# ten_peg_board.net
KiCad netlist of a schematic drawn in EAGLE
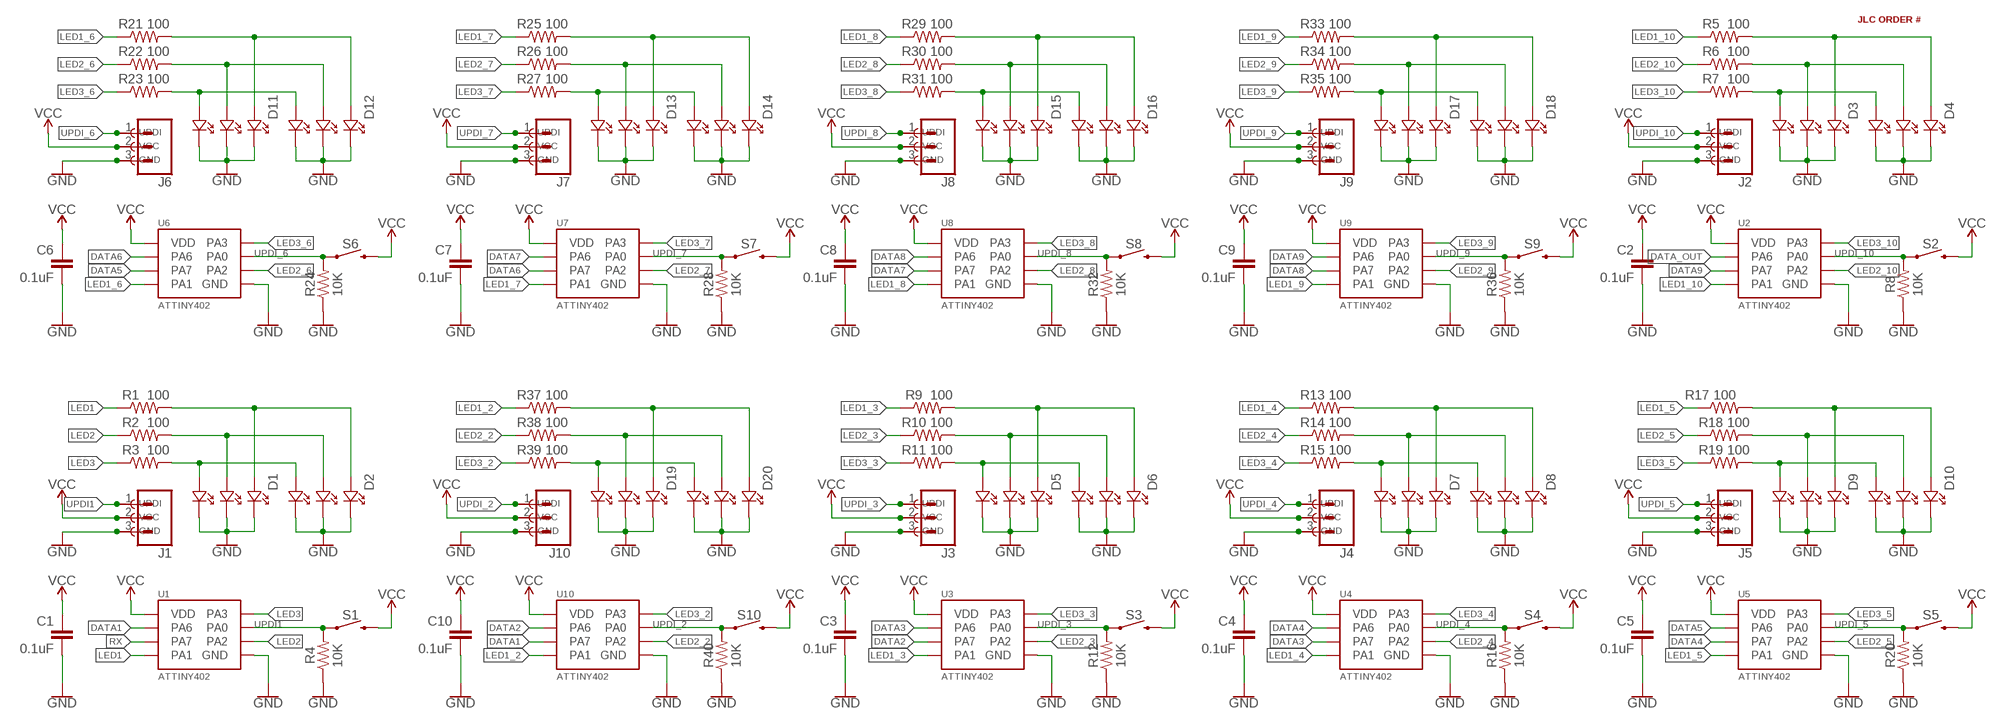
[diagram p0: schematic, sheet 1]

(export (version "E")
  (design (tool "Eeschema 10.0.6"))
  (components
    (comp (ref "C1")
      (value "0.1uF")
      (footprint "eagle-import:0603")
      (libsource (lib "eagle-import") (part "0.1UF-0603-25V-(+80/-20%)"))
    )
    (comp (ref "C2")
      (value "0.1uF")
      (footprint "eagle-import:0603")
      (libsource (lib "eagle-import") (part "0.1UF-0603-25V-(+80/-20%)"))
    )
    (comp (ref "C3")
      (value "0.1uF")
      (footprint "eagle-import:0603")
      (libsource (lib "eagle-import") (part "0.1UF-0603-25V-(+80/-20%)"))
    )
    (comp (ref "C4")
      (value "0.1uF")
      (footprint "eagle-import:0603")
      (libsource (lib "eagle-import") (part "0.1UF-0603-25V-(+80/-20%)"))
    )
    (comp (ref "C5")
      (value "0.1uF")
      (footprint "eagle-import:0603")
      (libsource (lib "eagle-import") (part "0.1UF-0603-25V-(+80/-20%)"))
    )
    (comp (ref "C6")
      (value "0.1uF")
      (footprint "eagle-import:0603")
      (libsource (lib "eagle-import") (part "0.1UF-0603-25V-(+80/-20%)"))
    )
    (comp (ref "C7")
      (value "0.1uF")
      (footprint "eagle-import:0603")
      (libsource (lib "eagle-import") (part "0.1UF-0603-25V-(+80/-20%)"))
    )
    (comp (ref "C8")
      (value "0.1uF")
      (footprint "eagle-import:0603")
      (libsource (lib "eagle-import") (part "0.1UF-0603-25V-(+80/-20%)"))
    )
    (comp (ref "C9")
      (value "0.1uF")
      (footprint "eagle-import:0603")
      (libsource (lib "eagle-import") (part "0.1UF-0603-25V-(+80/-20%)"))
    )
    (comp (ref "C10")
      (value "0.1uF")
      (footprint "eagle-import:0603")
      (libsource (lib "eagle-import") (part "0.1UF-0603-25V-(+80/-20%)"))
    )
    (comp (ref "D1")
      (value "19-337C/RSBHGHC-A88/4T")
      (footprint "eagle-import:6-SMD")
      (libsource (lib "eagle-import") (part "19-337C/RSBHGHC-A88/4T"))
    )
    (comp (ref "D2")
      (value "19-337C/RSBHGHC-A88/4T")
      (footprint "eagle-import:6-SMD")
      (libsource (lib "eagle-import") (part "19-337C/RSBHGHC-A88/4T"))
    )
    (comp (ref "D3")
      (value "19-337C/RSBHGHC-A88/4T")
      (footprint "eagle-import:6-SMD")
      (libsource (lib "eagle-import") (part "19-337C/RSBHGHC-A88/4T"))
    )
    (comp (ref "D4")
      (value "19-337C/RSBHGHC-A88/4T")
      (footprint "eagle-import:6-SMD")
      (libsource (lib "eagle-import") (part "19-337C/RSBHGHC-A88/4T"))
    )
    (comp (ref "D5")
      (value "19-337C/RSBHGHC-A88/4T")
      (footprint "eagle-import:6-SMD")
      (libsource (lib "eagle-import") (part "19-337C/RSBHGHC-A88/4T"))
    )
    (comp (ref "D6")
      (value "19-337C/RSBHGHC-A88/4T")
      (footprint "eagle-import:6-SMD")
      (libsource (lib "eagle-import") (part "19-337C/RSBHGHC-A88/4T"))
    )
    (comp (ref "D7")
      (value "19-337C/RSBHGHC-A88/4T")
      (footprint "eagle-import:6-SMD")
      (libsource (lib "eagle-import") (part "19-337C/RSBHGHC-A88/4T"))
    )
    (comp (ref "D8")
      (value "19-337C/RSBHGHC-A88/4T")
      (footprint "eagle-import:6-SMD")
      (libsource (lib "eagle-import") (part "19-337C/RSBHGHC-A88/4T"))
    )
    (comp (ref "D9")
      (value "19-337C/RSBHGHC-A88/4T")
      (footprint "eagle-import:6-SMD")
      (libsource (lib "eagle-import") (part "19-337C/RSBHGHC-A88/4T"))
    )
    (comp (ref "D10")
      (value "19-337C/RSBHGHC-A88/4T")
      (footprint "eagle-import:6-SMD")
      (libsource (lib "eagle-import") (part "19-337C/RSBHGHC-A88/4T"))
    )
    (comp (ref "D11")
      (value "19-337C/RSBHGHC-A88/4T")
      (footprint "eagle-import:6-SMD")
      (libsource (lib "eagle-import") (part "19-337C/RSBHGHC-A88/4T"))
    )
    (comp (ref "D12")
      (value "19-337C/RSBHGHC-A88/4T")
      (footprint "eagle-import:6-SMD")
      (libsource (lib "eagle-import") (part "19-337C/RSBHGHC-A88/4T"))
    )
    (comp (ref "D13")
      (value "19-337C/RSBHGHC-A88/4T")
      (footprint "eagle-import:6-SMD")
      (libsource (lib "eagle-import") (part "19-337C/RSBHGHC-A88/4T"))
    )
    (comp (ref "D14")
      (value "19-337C/RSBHGHC-A88/4T")
      (footprint "eagle-import:6-SMD")
      (libsource (lib "eagle-import") (part "19-337C/RSBHGHC-A88/4T"))
    )
    (comp (ref "D15")
      (value "19-337C/RSBHGHC-A88/4T")
      (footprint "eagle-import:6-SMD")
      (libsource (lib "eagle-import") (part "19-337C/RSBHGHC-A88/4T"))
    )
    (comp (ref "D16")
      (value "19-337C/RSBHGHC-A88/4T")
      (footprint "eagle-import:6-SMD")
      (libsource (lib "eagle-import") (part "19-337C/RSBHGHC-A88/4T"))
    )
    (comp (ref "D17")
      (value "19-337C/RSBHGHC-A88/4T")
      (footprint "eagle-import:6-SMD")
      (libsource (lib "eagle-import") (part "19-337C/RSBHGHC-A88/4T"))
    )
    (comp (ref "D18")
      (value "19-337C/RSBHGHC-A88/4T")
      (footprint "eagle-import:6-SMD")
      (libsource (lib "eagle-import") (part "19-337C/RSBHGHC-A88/4T"))
    )
    (comp (ref "D19")
      (value "19-337C/RSBHGHC-A88/4T")
      (footprint "eagle-import:6-SMD")
      (libsource (lib "eagle-import") (part "19-337C/RSBHGHC-A88/4T"))
    )
    (comp (ref "D20")
      (value "19-337C/RSBHGHC-A88/4T")
      (footprint "eagle-import:6-SMD")
      (libsource (lib "eagle-import") (part "19-337C/RSBHGHC-A88/4T"))
    )
    (comp (ref "J1")
      (value "CONN_03LOCK_LONGPADS")
      (footprint "eagle-import:1X03_LOCK_LONGPADS")
      (libsource (lib "eagle-import") (part "CONN_03LOCK_LONGPADS"))
    )
    (comp (ref "J2")
      (value "CONN_03LOCK_LONGPADS")
      (footprint "eagle-import:1X03_LOCK_LONGPADS")
      (libsource (lib "eagle-import") (part "CONN_03LOCK_LONGPADS"))
    )
    (comp (ref "J3")
      (value "CONN_03LOCK_LONGPADS")
      (footprint "eagle-import:1X03_LOCK_LONGPADS")
      (libsource (lib "eagle-import") (part "CONN_03LOCK_LONGPADS"))
    )
    (comp (ref "J4")
      (value "CONN_03LOCK_LONGPADS")
      (footprint "eagle-import:1X03_LOCK_LONGPADS")
      (libsource (lib "eagle-import") (part "CONN_03LOCK_LONGPADS"))
    )
    (comp (ref "J5")
      (value "CONN_03LOCK_LONGPADS")
      (footprint "eagle-import:1X03_LOCK_LONGPADS")
      (libsource (lib "eagle-import") (part "CONN_03LOCK_LONGPADS"))
    )
    (comp (ref "J6")
      (value "CONN_03LOCK_LONGPADS")
      (footprint "eagle-import:1X03_LOCK_LONGPADS")
      (libsource (lib "eagle-import") (part "CONN_03LOCK_LONGPADS"))
    )
    (comp (ref "J7")
      (value "CONN_03LOCK_LONGPADS")
      (footprint "eagle-import:1X03_LOCK_LONGPADS")
      (libsource (lib "eagle-import") (part "CONN_03LOCK_LONGPADS"))
    )
    (comp (ref "J8")
      (value "CONN_03LOCK_LONGPADS")
      (footprint "eagle-import:1X03_LOCK_LONGPADS")
      (libsource (lib "eagle-import") (part "CONN_03LOCK_LONGPADS"))
    )
    (comp (ref "J9")
      (value "CONN_03LOCK_LONGPADS")
      (footprint "eagle-import:1X03_LOCK_LONGPADS")
      (libsource (lib "eagle-import") (part "CONN_03LOCK_LONGPADS"))
    )
    (comp (ref "J10")
      (value "CONN_03LOCK_LONGPADS")
      (footprint "eagle-import:1X03_LOCK_LONGPADS")
      (libsource (lib "eagle-import") (part "CONN_03LOCK_LONGPADS"))
    )
    (comp (ref "R1")
      (value "100")
      (footprint "eagle-import:0603")
      (libsource (lib "eagle-import") (part "100OHM-0603-1/4W-5%"))
    )
    (comp (ref "R2")
      (value "100")
      (footprint "eagle-import:0603")
      (libsource (lib "eagle-import") (part "100OHM-0603-1/4W-5%"))
    )
    (comp (ref "R3")
      (value "100")
      (footprint "eagle-import:0603")
      (libsource (lib "eagle-import") (part "100OHM-0603-1/4W-5%"))
    )
    (comp (ref "R4")
      (value "10K")
      (footprint "eagle-import:0603")
      (libsource (lib "eagle-import") (part "100OHM-0603-1/4W-5%"))
    )
    (comp (ref "R5")
      (value "100")
      (footprint "eagle-import:0603")
      (libsource (lib "eagle-import") (part "100OHM-0603-1/4W-5%"))
    )
    (comp (ref "R6")
      (value "100")
      (footprint "eagle-import:0603")
      (libsource (lib "eagle-import") (part "100OHM-0603-1/4W-5%"))
    )
    (comp (ref "R7")
      (value "100")
      (footprint "eagle-import:0603")
      (libsource (lib "eagle-import") (part "100OHM-0603-1/4W-5%"))
    )
    (comp (ref "R8")
      (value "10K")
      (footprint "eagle-import:0603")
      (libsource (lib "eagle-import") (part "100OHM-0603-1/4W-5%"))
    )
    (comp (ref "R9")
      (value "100")
      (footprint "eagle-import:0603")
      (libsource (lib "eagle-import") (part "100OHM-0603-1/4W-5%"))
    )
    (comp (ref "R10")
      (value "100")
      (footprint "eagle-import:0603")
      (libsource (lib "eagle-import") (part "100OHM-0603-1/4W-5%"))
    )
    (comp (ref "R11")
      (value "100")
      (footprint "eagle-import:0603")
      (libsource (lib "eagle-import") (part "100OHM-0603-1/4W-5%"))
    )
    (comp (ref "R12")
      (value "10K")
      (footprint "eagle-import:0603")
      (libsource (lib "eagle-import") (part "100OHM-0603-1/4W-5%"))
    )
    (comp (ref "R13")
      (value "100")
      (footprint "eagle-import:0603")
      (libsource (lib "eagle-import") (part "100OHM-0603-1/4W-5%"))
    )
    (comp (ref "R14")
      (value "100")
      (footprint "eagle-import:0603")
      (libsource (lib "eagle-import") (part "100OHM-0603-1/4W-5%"))
    )
    (comp (ref "R15")
      (value "100")
      (footprint "eagle-import:0603")
      (libsource (lib "eagle-import") (part "100OHM-0603-1/4W-5%"))
    )
    (comp (ref "R16")
      (value "10K")
      (footprint "eagle-import:0603")
      (libsource (lib "eagle-import") (part "100OHM-0603-1/4W-5%"))
    )
    (comp (ref "R17")
      (value "100")
      (footprint "eagle-import:0603")
      (libsource (lib "eagle-import") (part "100OHM-0603-1/4W-5%"))
    )
    (comp (ref "R18")
      (value "100")
      (footprint "eagle-import:0603")
      (libsource (lib "eagle-import") (part "100OHM-0603-1/4W-5%"))
    )
    (comp (ref "R19")
      (value "100")
      (footprint "eagle-import:0603")
      (libsource (lib "eagle-import") (part "100OHM-0603-1/4W-5%"))
    )
    (comp (ref "R20")
      (value "10K")
      (footprint "eagle-import:0603")
      (libsource (lib "eagle-import") (part "100OHM-0603-1/4W-5%"))
    )
    (comp (ref "R21")
      (value "100")
      (footprint "eagle-import:0603")
      (libsource (lib "eagle-import") (part "100OHM-0603-1/4W-5%"))
    )
    (comp (ref "R22")
      (value "100")
      (footprint "eagle-import:0603")
      (libsource (lib "eagle-import") (part "100OHM-0603-1/4W-5%"))
    )
    (comp (ref "R23")
      (value "100")
      (footprint "eagle-import:0603")
      (libsource (lib "eagle-import") (part "100OHM-0603-1/4W-5%"))
    )
    (comp (ref "R24")
      (value "10K")
      (footprint "eagle-import:0603")
      (libsource (lib "eagle-import") (part "100OHM-0603-1/4W-5%"))
    )
    (comp (ref "R25")
      (value "100")
      (footprint "eagle-import:0603")
      (libsource (lib "eagle-import") (part "100OHM-0603-1/4W-5%"))
    )
    (comp (ref "R26")
      (value "100")
      (footprint "eagle-import:0603")
      (libsource (lib "eagle-import") (part "100OHM-0603-1/4W-5%"))
    )
    (comp (ref "R27")
      (value "100")
      (footprint "eagle-import:0603")
      (libsource (lib "eagle-import") (part "100OHM-0603-1/4W-5%"))
    )
    (comp (ref "R28")
      (value "10K")
      (footprint "eagle-import:0603")
      (libsource (lib "eagle-import") (part "100OHM-0603-1/4W-5%"))
    )
    (comp (ref "R29")
      (value "100")
      (footprint "eagle-import:0603")
      (libsource (lib "eagle-import") (part "100OHM-0603-1/4W-5%"))
    )
    (comp (ref "R30")
      (value "100")
      (footprint "eagle-import:0603")
      (libsource (lib "eagle-import") (part "100OHM-0603-1/4W-5%"))
    )
    (comp (ref "R31")
      (value "100")
      (footprint "eagle-import:0603")
      (libsource (lib "eagle-import") (part "100OHM-0603-1/4W-5%"))
    )
    (comp (ref "R32")
      (value "10K")
      (footprint "eagle-import:0603")
      (libsource (lib "eagle-import") (part "100OHM-0603-1/4W-5%"))
    )
    (comp (ref "R33")
      (value "100")
      (footprint "eagle-import:0603")
      (libsource (lib "eagle-import") (part "100OHM-0603-1/4W-5%"))
    )
    (comp (ref "R34")
      (value "100")
      (footprint "eagle-import:0603")
      (libsource (lib "eagle-import") (part "100OHM-0603-1/4W-5%"))
    )
    (comp (ref "R35")
      (value "100")
      (footprint "eagle-import:0603")
      (libsource (lib "eagle-import") (part "100OHM-0603-1/4W-5%"))
    )
    (comp (ref "R36")
      (value "10K")
      (footprint "eagle-import:0603")
      (libsource (lib "eagle-import") (part "100OHM-0603-1/4W-5%"))
    )
    (comp (ref "R37")
      (value "100")
      (footprint "eagle-import:0603")
      (libsource (lib "eagle-import") (part "100OHM-0603-1/4W-5%"))
    )
    (comp (ref "R38")
      (value "100")
      (footprint "eagle-import:0603")
      (libsource (lib "eagle-import") (part "100OHM-0603-1/4W-5%"))
    )
    (comp (ref "R39")
      (value "100")
      (footprint "eagle-import:0603")
      (libsource (lib "eagle-import") (part "100OHM-0603-1/4W-5%"))
    )
    (comp (ref "R40")
      (value "10K")
      (footprint "eagle-import:0603")
      (libsource (lib "eagle-import") (part "100OHM-0603-1/4W-5%"))
    )
    (comp (ref "S1")
      (value "MOMENTARY-SWITCH-SPST-SMD-4.5MM-WINGED")
      (footprint "eagle-import:TACTILE_SWITCH_SMD_4.5MM_WINGED")
      (libsource (lib "eagle-import") (part "MOMENTARY-SWITCH-SPST-SMD-4.5MM-WINGED"))
    )
    (comp (ref "S2")
      (value "MOMENTARY-SWITCH-SPST-SMD-4.5MM-WINGED")
      (footprint "eagle-import:TACTILE_SWITCH_SMD_4.5MM_WINGED")
      (libsource (lib "eagle-import") (part "MOMENTARY-SWITCH-SPST-SMD-4.5MM-WINGED"))
    )
    (comp (ref "S3")
      (value "MOMENTARY-SWITCH-SPST-SMD-4.5MM-WINGED")
      (footprint "eagle-import:TACTILE_SWITCH_SMD_4.5MM_WINGED")
      (libsource (lib "eagle-import") (part "MOMENTARY-SWITCH-SPST-SMD-4.5MM-WINGED"))
    )
    (comp (ref "S4")
      (value "MOMENTARY-SWITCH-SPST-SMD-4.5MM-WINGED")
      (footprint "eagle-import:TACTILE_SWITCH_SMD_4.5MM_WINGED")
      (libsource (lib "eagle-import") (part "MOMENTARY-SWITCH-SPST-SMD-4.5MM-WINGED"))
    )
    (comp (ref "S5")
      (value "MOMENTARY-SWITCH-SPST-SMD-4.5MM-WINGED")
      (footprint "eagle-import:TACTILE_SWITCH_SMD_4.5MM_WINGED")
      (libsource (lib "eagle-import") (part "MOMENTARY-SWITCH-SPST-SMD-4.5MM-WINGED"))
    )
    (comp (ref "S6")
      (value "MOMENTARY-SWITCH-SPST-SMD-4.5MM-WINGED")
      (footprint "eagle-import:TACTILE_SWITCH_SMD_4.5MM_WINGED")
      (libsource (lib "eagle-import") (part "MOMENTARY-SWITCH-SPST-SMD-4.5MM-WINGED"))
    )
    (comp (ref "S7")
      (value "MOMENTARY-SWITCH-SPST-SMD-4.5MM-WINGED")
      (footprint "eagle-import:TACTILE_SWITCH_SMD_4.5MM_WINGED")
      (libsource (lib "eagle-import") (part "MOMENTARY-SWITCH-SPST-SMD-4.5MM-WINGED"))
    )
    (comp (ref "S8")
      (value "MOMENTARY-SWITCH-SPST-SMD-4.5MM-WINGED")
      (footprint "eagle-import:TACTILE_SWITCH_SMD_4.5MM_WINGED")
      (libsource (lib "eagle-import") (part "MOMENTARY-SWITCH-SPST-SMD-4.5MM-WINGED"))
    )
    (comp (ref "S9")
      (value "MOMENTARY-SWITCH-SPST-SMD-4.5MM-WINGED")
      (footprint "eagle-import:TACTILE_SWITCH_SMD_4.5MM_WINGED")
      (libsource (lib "eagle-import") (part "MOMENTARY-SWITCH-SPST-SMD-4.5MM-WINGED"))
    )
    (comp (ref "S10")
      (value "MOMENTARY-SWITCH-SPST-SMD-4.5MM-WINGED")
      (footprint "eagle-import:TACTILE_SWITCH_SMD_4.5MM_WINGED")
      (libsource (lib "eagle-import") (part "MOMENTARY-SWITCH-SPST-SMD-4.5MM-WINGED"))
    )
    (comp (ref "TP1")
      (value "TEST-POINT3X5")
      (footprint "eagle-import:PAD.03X.05")
      (libsource (lib "eagle-import") (part "TEST-POINT3X5"))
    )
    (comp (ref "TP2")
      (value "TEST-POINT3X5")
      (footprint "eagle-import:PAD.03X.05")
      (libsource (lib "eagle-import") (part "TEST-POINT3X5"))
    )
    (comp (ref "TP3")
      (value "TEST-POINT3X5")
      (footprint "eagle-import:PAD.03X.05")
      (libsource (lib "eagle-import") (part "TEST-POINT3X5"))
    )
    (comp (ref "TP4")
      (value "TEST-POINT3X5")
      (footprint "eagle-import:PAD.03X.05")
      (libsource (lib "eagle-import") (part "TEST-POINT3X5"))
    )
    (comp (ref "TP5")
      (value "TEST-POINT3X5")
      (footprint "eagle-import:PAD.03X.05")
      (libsource (lib "eagle-import") (part "TEST-POINT3X5"))
    )
    (comp (ref "TP6")
      (value "TEST-POINT3X5")
      (footprint "eagle-import:PAD.03X.05")
      (libsource (lib "eagle-import") (part "TEST-POINT3X5"))
    )
    (comp (ref "TP7")
      (value "TEST-POINT3X5")
      (footprint "eagle-import:PAD.03X.05")
      (libsource (lib "eagle-import") (part "TEST-POINT3X5"))
    )
    (comp (ref "TP8")
      (value "TEST-POINT3X5")
      (footprint "eagle-import:PAD.03X.05")
      (libsource (lib "eagle-import") (part "TEST-POINT3X5"))
    )
    (comp (ref "TP9")
      (value "TEST-POINT3X5")
      (footprint "eagle-import:PAD.03X.05")
      (libsource (lib "eagle-import") (part "TEST-POINT3X5"))
    )
    (comp (ref "TP10")
      (value "TEST-POINT3X5")
      (footprint "eagle-import:PAD.03X.05")
      (libsource (lib "eagle-import") (part "TEST-POINT3X5"))
    )
    (comp (ref "TP11")
      (value "TEST-POINT3X5")
      (footprint "eagle-import:PAD.03X.05")
      (libsource (lib "eagle-import") (part "TEST-POINT3X5"))
    )
    (comp (ref "TP12")
      (value "TEST-POINT3X5")
      (footprint "eagle-import:PAD.03X.05")
      (libsource (lib "eagle-import") (part "TEST-POINT3X5"))
    )
    (comp (ref "TP13")
      (value "TEST-POINT3X5")
      (footprint "eagle-import:PAD.03X.05")
      (libsource (lib "eagle-import") (part "TEST-POINT3X5"))
    )
    (comp (ref "TP14")
      (value "TEST-POINT3X5")
      (footprint "eagle-import:PAD.03X.05")
      (libsource (lib "eagle-import") (part "TEST-POINT3X5"))
    )
    (comp (ref "TP15")
      (value "TEST-POINT3X5")
      (footprint "eagle-import:PAD.03X.05")
      (libsource (lib "eagle-import") (part "TEST-POINT3X5"))
    )
    (comp (ref "TP16")
      (value "TEST-POINT3X5")
      (footprint "eagle-import:PAD.03X.05")
      (libsource (lib "eagle-import") (part "TEST-POINT3X5"))
    )
    (comp (ref "TP17")
      (value "TEST-POINT3X5")
      (footprint "eagle-import:PAD.03X.05")
      (libsource (lib "eagle-import") (part "TEST-POINT3X5"))
    )
    (comp (ref "TP18")
      (value "TEST-POINT3X5")
      (footprint "eagle-import:PAD.03X.05")
      (libsource (lib "eagle-import") (part "TEST-POINT3X5"))
    )
    (comp (ref "TP19")
      (value "TEST-POINT3X5")
      (footprint "eagle-import:PAD.03X.05")
      (libsource (lib "eagle-import") (part "TEST-POINT3X5"))
    )
    (comp (ref "TP20")
      (value "TEST-POINT3X5")
      (footprint "eagle-import:PAD.03X.05")
      (libsource (lib "eagle-import") (part "TEST-POINT3X5"))
    )
    (comp (ref "TP21")
      (value "TEST-POINT3X5")
      (footprint "eagle-import:PAD.03X.05")
      (libsource (lib "eagle-import") (part "TEST-POINT3X5"))
    )
    (comp (ref "TP22")
      (value "TEST-POINT3X5")
      (footprint "eagle-import:PAD.03X.05")
      (libsource (lib "eagle-import") (part "TEST-POINT3X5"))
    )
    (comp (ref "TP23")
      (value "TEST-POINT3X5")
      (footprint "eagle-import:PAD.03X.05")
      (libsource (lib "eagle-import") (part "TEST-POINT3X5"))
    )
    (comp (ref "TP24")
      (value "TEST-POINT3X5")
      (footprint "eagle-import:PAD.03X.05")
      (libsource (lib "eagle-import") (part "TEST-POINT3X5"))
    )
    (comp (ref "TP25")
      (value "TEST-POINT3X5")
      (footprint "eagle-import:PAD.03X.05")
      (libsource (lib "eagle-import") (part "TEST-POINT3X5"))
    )
    (comp (ref "TP26")
      (value "TEST-POINT3X5")
      (footprint "eagle-import:PAD.03X.05")
      (libsource (lib "eagle-import") (part "TEST-POINT3X5"))
    )
    (comp (ref "TP27")
      (value "TEST-POINT3X5")
      (footprint "eagle-import:PAD.03X.05")
      (libsource (lib "eagle-import") (part "TEST-POINT3X5"))
    )
    (comp (ref "TP28")
      (value "TEST-POINT3X5")
      (footprint "eagle-import:PAD.03X.05")
      (libsource (lib "eagle-import") (part "TEST-POINT3X5"))
    )
    (comp (ref "TP29")
      (value "TEST-POINT3X5")
      (footprint "eagle-import:PAD.03X.05")
      (libsource (lib "eagle-import") (part "TEST-POINT3X5"))
    )
    (comp (ref "TP30")
      (value "TEST-POINT3X5")
      (footprint "eagle-import:PAD.03X.05")
      (libsource (lib "eagle-import") (part "TEST-POINT3X5"))
    )
    (comp (ref "U$1")
      (value "JLC-ORDER-NUMBER")
      (footprint "eagle-import:JLC_ORDER_NUMBER")
      (libsource (lib "eagle-import") (part "JLC-ORDER-NUMBER"))
    )
    (comp (ref "U1")
      (value "ATTINY402")
      (footprint "eagle-import:8-SOIC")
      (libsource (lib "eagle-import") (part "ATTINY402"))
    )
    (comp (ref "U2")
      (value "ATTINY402")
      (footprint "eagle-import:8-SOIC")
      (libsource (lib "eagle-import") (part "ATTINY402"))
    )
    (comp (ref "U3")
      (value "ATTINY402")
      (footprint "eagle-import:8-SOIC")
      (libsource (lib "eagle-import") (part "ATTINY402"))
    )
    (comp (ref "U4")
      (value "ATTINY402")
      (footprint "eagle-import:8-SOIC")
      (libsource (lib "eagle-import") (part "ATTINY402"))
    )
    (comp (ref "U5")
      (value "ATTINY402")
      (footprint "eagle-import:8-SOIC")
      (libsource (lib "eagle-import") (part "ATTINY402"))
    )
    (comp (ref "U6")
      (value "ATTINY402")
      (footprint "eagle-import:8-SOIC")
      (libsource (lib "eagle-import") (part "ATTINY402"))
    )
    (comp (ref "U7")
      (value "ATTINY402")
      (footprint "eagle-import:8-SOIC")
      (libsource (lib "eagle-import") (part "ATTINY402"))
    )
    (comp (ref "U8")
      (value "ATTINY402")
      (footprint "eagle-import:8-SOIC")
      (libsource (lib "eagle-import") (part "ATTINY402"))
    )
    (comp (ref "U9")
      (value "ATTINY402")
      (footprint "eagle-import:8-SOIC")
      (libsource (lib "eagle-import") (part "ATTINY402"))
    )
    (comp (ref "U10")
      (value "ATTINY402")
      (footprint "eagle-import:8-SOIC")
      (libsource (lib "eagle-import") (part "ATTINY402"))
    )
  )
  (nets
    (net (code "1") (name "DATA1") (class "Default")
      (node (ref "U1") (pin "P$2") (pinfunction "PA6_P$2") (pintype "bidirectional"))
      (node (ref "U10") (pin "P$3") (pinfunction "PA7_P$3") (pintype "bidirectional"))
    )
    (net (code "2") (name "DATA2") (class "Default")
      (node (ref "U10") (pin "P$2") (pinfunction "PA6_P$2") (pintype "bidirectional"))
      (node (ref "U3") (pin "P$3") (pinfunction "PA7_P$3") (pintype "bidirectional"))
    )
    (net (code "3") (name "DATA3") (class "Default")
      (node (ref "U3") (pin "P$2") (pinfunction "PA6_P$2") (pintype "bidirectional"))
      (node (ref "U4") (pin "P$3") (pinfunction "PA7_P$3") (pintype "bidirectional"))
    )
    (net (code "4") (name "DATA4") (class "Default")
      (node (ref "U4") (pin "P$2") (pinfunction "PA6_P$2") (pintype "bidirectional"))
      (node (ref "U5") (pin "P$3") (pinfunction "PA7_P$3") (pintype "bidirectional"))
    )
    (net (code "5") (name "DATA5") (class "Default")
      (node (ref "U5") (pin "P$2") (pinfunction "PA6_P$2") (pintype "bidirectional"))
      (node (ref "U6") (pin "P$3") (pinfunction "PA7_P$3") (pintype "bidirectional"))
    )
    (net (code "6") (name "DATA6") (class "Default")
      (node (ref "U6") (pin "P$2") (pinfunction "PA6_P$2") (pintype "bidirectional"))
      (node (ref "U7") (pin "P$3") (pinfunction "PA7_P$3") (pintype "bidirectional"))
    )
    (net (code "7") (name "DATA7") (class "Default")
      (node (ref "U7") (pin "P$2") (pinfunction "PA6_P$2") (pintype "bidirectional"))
      (node (ref "U8") (pin "P$3") (pinfunction "PA7_P$3") (pintype "bidirectional"))
    )
    (net (code "8") (name "DATA8") (class "Default")
      (node (ref "U8") (pin "P$2") (pinfunction "PA6_P$2") (pintype "bidirectional"))
      (node (ref "U9") (pin "P$3") (pinfunction "PA7_P$3") (pintype "bidirectional"))
    )
    (net (code "9") (name "DATA9") (class "Default")
      (node (ref "U2") (pin "P$3") (pinfunction "PA7_P$3") (pintype "bidirectional"))
      (node (ref "U9") (pin "P$2") (pinfunction "PA6_P$2") (pintype "bidirectional"))
    )
    (net (code "10") (name "DATA_OUT") (class "Default")
      (node (ref "U2") (pin "P$2") (pinfunction "PA6_P$2") (pintype "bidirectional"))
    )
    (net (code "11") (name "GND") (class "Default")
      (node (ref "C1") (pin "2") (pinfunction "2_2") (pintype "passive"))
      (node (ref "C10") (pin "2") (pinfunction "2_2") (pintype "passive"))
      (node (ref "C2") (pin "2") (pinfunction "2_2") (pintype "passive"))
      (node (ref "C3") (pin "2") (pinfunction "2_2") (pintype "passive"))
      (node (ref "C4") (pin "2") (pinfunction "2_2") (pintype "passive"))
      (node (ref "C5") (pin "2") (pinfunction "2_2") (pintype "passive"))
      (node (ref "C6") (pin "2") (pinfunction "2_2") (pintype "passive"))
      (node (ref "C7") (pin "2") (pinfunction "2_2") (pintype "passive"))
      (node (ref "C8") (pin "2") (pinfunction "2_2") (pintype "passive"))
      (node (ref "C9") (pin "2") (pinfunction "2_2") (pintype "passive"))
      (node (ref "D1") (pin "P$1") (pinfunction "P$1_P$1") (pintype "bidirectional"))
      (node (ref "D1") (pin "P$3") (pinfunction "P$3_P$3") (pintype "bidirectional"))
      (node (ref "D1") (pin "P$5") (pinfunction "P$5_P$5") (pintype "bidirectional"))
      (node (ref "D10") (pin "P$1") (pinfunction "P$1_P$1") (pintype "bidirectional"))
      (node (ref "D10") (pin "P$3") (pinfunction "P$3_P$3") (pintype "bidirectional"))
      (node (ref "D10") (pin "P$5") (pinfunction "P$5_P$5") (pintype "bidirectional"))
      (node (ref "D11") (pin "P$1") (pinfunction "P$1_P$1") (pintype "bidirectional"))
      (node (ref "D11") (pin "P$3") (pinfunction "P$3_P$3") (pintype "bidirectional"))
      (node (ref "D11") (pin "P$5") (pinfunction "P$5_P$5") (pintype "bidirectional"))
      (node (ref "D12") (pin "P$1") (pinfunction "P$1_P$1") (pintype "bidirectional"))
      (node (ref "D12") (pin "P$3") (pinfunction "P$3_P$3") (pintype "bidirectional"))
      (node (ref "D12") (pin "P$5") (pinfunction "P$5_P$5") (pintype "bidirectional"))
      (node (ref "D13") (pin "P$1") (pinfunction "P$1_P$1") (pintype "bidirectional"))
      (node (ref "D13") (pin "P$3") (pinfunction "P$3_P$3") (pintype "bidirectional"))
      (node (ref "D13") (pin "P$5") (pinfunction "P$5_P$5") (pintype "bidirectional"))
      (node (ref "D14") (pin "P$1") (pinfunction "P$1_P$1") (pintype "bidirectional"))
      (node (ref "D14") (pin "P$3") (pinfunction "P$3_P$3") (pintype "bidirectional"))
      (node (ref "D14") (pin "P$5") (pinfunction "P$5_P$5") (pintype "bidirectional"))
      (node (ref "D15") (pin "P$1") (pinfunction "P$1_P$1") (pintype "bidirectional"))
      (node (ref "D15") (pin "P$3") (pinfunction "P$3_P$3") (pintype "bidirectional"))
      (node (ref "D15") (pin "P$5") (pinfunction "P$5_P$5") (pintype "bidirectional"))
      (node (ref "D16") (pin "P$1") (pinfunction "P$1_P$1") (pintype "bidirectional"))
      (node (ref "D16") (pin "P$3") (pinfunction "P$3_P$3") (pintype "bidirectional"))
      (node (ref "D16") (pin "P$5") (pinfunction "P$5_P$5") (pintype "bidirectional"))
      (node (ref "D17") (pin "P$1") (pinfunction "P$1_P$1") (pintype "bidirectional"))
      (node (ref "D17") (pin "P$3") (pinfunction "P$3_P$3") (pintype "bidirectional"))
      (node (ref "D17") (pin "P$5") (pinfunction "P$5_P$5") (pintype "bidirectional"))
      (node (ref "D18") (pin "P$1") (pinfunction "P$1_P$1") (pintype "bidirectional"))
      (node (ref "D18") (pin "P$3") (pinfunction "P$3_P$3") (pintype "bidirectional"))
      (node (ref "D18") (pin "P$5") (pinfunction "P$5_P$5") (pintype "bidirectional"))
      (node (ref "D19") (pin "P$1") (pinfunction "P$1_P$1") (pintype "bidirectional"))
      (node (ref "D19") (pin "P$3") (pinfunction "P$3_P$3") (pintype "bidirectional"))
      (node (ref "D19") (pin "P$5") (pinfunction "P$5_P$5") (pintype "bidirectional"))
      (node (ref "D2") (pin "P$1") (pinfunction "P$1_P$1") (pintype "bidirectional"))
      (node (ref "D2") (pin "P$3") (pinfunction "P$3_P$3") (pintype "bidirectional"))
      (node (ref "D2") (pin "P$5") (pinfunction "P$5_P$5") (pintype "bidirectional"))
      (node (ref "D20") (pin "P$1") (pinfunction "P$1_P$1") (pintype "bidirectional"))
      (node (ref "D20") (pin "P$3") (pinfunction "P$3_P$3") (pintype "bidirectional"))
      (node (ref "D20") (pin "P$5") (pinfunction "P$5_P$5") (pintype "bidirectional"))
      (node (ref "D3") (pin "P$1") (pinfunction "P$1_P$1") (pintype "bidirectional"))
      (node (ref "D3") (pin "P$3") (pinfunction "P$3_P$3") (pintype "bidirectional"))
      (node (ref "D3") (pin "P$5") (pinfunction "P$5_P$5") (pintype "bidirectional"))
      (node (ref "D4") (pin "P$1") (pinfunction "P$1_P$1") (pintype "bidirectional"))
      (node (ref "D4") (pin "P$3") (pinfunction "P$3_P$3") (pintype "bidirectional"))
      (node (ref "D4") (pin "P$5") (pinfunction "P$5_P$5") (pintype "bidirectional"))
      (node (ref "D5") (pin "P$1") (pinfunction "P$1_P$1") (pintype "bidirectional"))
      (node (ref "D5") (pin "P$3") (pinfunction "P$3_P$3") (pintype "bidirectional"))
      (node (ref "D5") (pin "P$5") (pinfunction "P$5_P$5") (pintype "bidirectional"))
      (node (ref "D6") (pin "P$1") (pinfunction "P$1_P$1") (pintype "bidirectional"))
      (node (ref "D6") (pin "P$3") (pinfunction "P$3_P$3") (pintype "bidirectional"))
      (node (ref "D6") (pin "P$5") (pinfunction "P$5_P$5") (pintype "bidirectional"))
      (node (ref "D7") (pin "P$1") (pinfunction "P$1_P$1") (pintype "bidirectional"))
      (node (ref "D7") (pin "P$3") (pinfunction "P$3_P$3") (pintype "bidirectional"))
      (node (ref "D7") (pin "P$5") (pinfunction "P$5_P$5") (pintype "bidirectional"))
      (node (ref "D8") (pin "P$1") (pinfunction "P$1_P$1") (pintype "bidirectional"))
      (node (ref "D8") (pin "P$3") (pinfunction "P$3_P$3") (pintype "bidirectional"))
      (node (ref "D8") (pin "P$5") (pinfunction "P$5_P$5") (pintype "bidirectional"))
      (node (ref "D9") (pin "P$1") (pinfunction "P$1_P$1") (pintype "bidirectional"))
      (node (ref "D9") (pin "P$3") (pinfunction "P$3_P$3") (pintype "bidirectional"))
      (node (ref "D9") (pin "P$5") (pinfunction "P$5_P$5") (pintype "bidirectional"))
      (node (ref "J1") (pin "3") (pinfunction "3_3") (pintype "passive"))
      (node (ref "J10") (pin "3") (pinfunction "3_3") (pintype "passive"))
      (node (ref "J2") (pin "3") (pinfunction "3_3") (pintype "passive"))
      (node (ref "J3") (pin "3") (pinfunction "3_3") (pintype "passive"))
      (node (ref "J4") (pin "3") (pinfunction "3_3") (pintype "passive"))
      (node (ref "J5") (pin "3") (pinfunction "3_3") (pintype "passive"))
      (node (ref "J6") (pin "3") (pinfunction "3_3") (pintype "passive"))
      (node (ref "J7") (pin "3") (pinfunction "3_3") (pintype "passive"))
      (node (ref "J8") (pin "3") (pinfunction "3_3") (pintype "passive"))
      (node (ref "J9") (pin "3") (pinfunction "3_3") (pintype "passive"))
      (node (ref "R12") (pin "1") (pinfunction "1_1") (pintype "passive"))
      (node (ref "R16") (pin "1") (pinfunction "1_1") (pintype "passive"))
      (node (ref "R20") (pin "1") (pinfunction "1_1") (pintype "passive"))
      (node (ref "R24") (pin "1") (pinfunction "1_1") (pintype "passive"))
      (node (ref "R28") (pin "1") (pinfunction "1_1") (pintype "passive"))
      (node (ref "R32") (pin "1") (pinfunction "1_1") (pintype "passive"))
      (node (ref "R36") (pin "1") (pinfunction "1_1") (pintype "passive"))
      (node (ref "R4") (pin "1") (pinfunction "1_1") (pintype "passive"))
      (node (ref "R40") (pin "1") (pinfunction "1_1") (pintype "passive"))
      (node (ref "R8") (pin "1") (pinfunction "1_1") (pintype "passive"))
      (node (ref "TP12") (pin "P$1") (pinfunction "1_P$1") (pintype "bidirectional"))
      (node (ref "TP15") (pin "P$1") (pinfunction "1_P$1") (pintype "bidirectional"))
      (node (ref "TP18") (pin "P$1") (pinfunction "1_P$1") (pintype "bidirectional"))
      (node (ref "TP21") (pin "P$1") (pinfunction "1_P$1") (pintype "bidirectional"))
      (node (ref "TP24") (pin "P$1") (pinfunction "1_P$1") (pintype "bidirectional"))
      (node (ref "TP27") (pin "P$1") (pinfunction "1_P$1") (pintype "bidirectional"))
      (node (ref "TP3") (pin "P$1") (pinfunction "1_P$1") (pintype "bidirectional"))
      (node (ref "TP30") (pin "P$1") (pinfunction "1_P$1") (pintype "bidirectional"))
      (node (ref "TP6") (pin "P$1") (pinfunction "1_P$1") (pintype "bidirectional"))
      (node (ref "TP9") (pin "P$1") (pinfunction "1_P$1") (pintype "bidirectional"))
      (node (ref "U1") (pin "P$8") (pinfunction "GND_P$8") (pintype "bidirectional"))
      (node (ref "U10") (pin "P$8") (pinfunction "GND_P$8") (pintype "bidirectional"))
      (node (ref "U2") (pin "P$8") (pinfunction "GND_P$8") (pintype "bidirectional"))
      (node (ref "U3") (pin "P$8") (pinfunction "GND_P$8") (pintype "bidirectional"))
      (node (ref "U4") (pin "P$8") (pinfunction "GND_P$8") (pintype "bidirectional"))
      (node (ref "U5") (pin "P$8") (pinfunction "GND_P$8") (pintype "bidirectional"))
      (node (ref "U6") (pin "P$8") (pinfunction "GND_P$8") (pintype "bidirectional"))
      (node (ref "U7") (pin "P$8") (pinfunction "GND_P$8") (pintype "bidirectional"))
      (node (ref "U8") (pin "P$8") (pinfunction "GND_P$8") (pintype "bidirectional"))
      (node (ref "U9") (pin "P$8") (pinfunction "GND_P$8") (pintype "bidirectional"))
    )
    (net (code "12") (name "LED1") (class "Default")
      (node (ref "R1") (pin "1") (pinfunction "1_1") (pintype "passive"))
      (node (ref "U1") (pin "P$4") (pinfunction "PA1_P$4") (pintype "bidirectional"))
    )
    (net (code "13") (name "LED1_2") (class "Default")
      (node (ref "R37") (pin "1") (pinfunction "1_1") (pintype "passive"))
      (node (ref "U10") (pin "P$4") (pinfunction "PA1_P$4") (pintype "bidirectional"))
    )
    (net (code "14") (name "LED1_3") (class "Default")
      (node (ref "R9") (pin "1") (pinfunction "1_1") (pintype "passive"))
      (node (ref "U3") (pin "P$4") (pinfunction "PA1_P$4") (pintype "bidirectional"))
    )
    (net (code "15") (name "LED1_4") (class "Default")
      (node (ref "R13") (pin "1") (pinfunction "1_1") (pintype "passive"))
      (node (ref "U4") (pin "P$4") (pinfunction "PA1_P$4") (pintype "bidirectional"))
    )
    (net (code "16") (name "LED1_5") (class "Default")
      (node (ref "R17") (pin "1") (pinfunction "1_1") (pintype "passive"))
      (node (ref "U5") (pin "P$4") (pinfunction "PA1_P$4") (pintype "bidirectional"))
    )
    (net (code "17") (name "LED1_6") (class "Default")
      (node (ref "R21") (pin "1") (pinfunction "1_1") (pintype "passive"))
      (node (ref "U6") (pin "P$4") (pinfunction "PA1_P$4") (pintype "bidirectional"))
    )
    (net (code "18") (name "LED1_7") (class "Default")
      (node (ref "R25") (pin "1") (pinfunction "1_1") (pintype "passive"))
      (node (ref "U7") (pin "P$4") (pinfunction "PA1_P$4") (pintype "bidirectional"))
    )
    (net (code "19") (name "LED1_8") (class "Default")
      (node (ref "R29") (pin "1") (pinfunction "1_1") (pintype "passive"))
      (node (ref "U8") (pin "P$4") (pinfunction "PA1_P$4") (pintype "bidirectional"))
    )
    (net (code "20") (name "LED1_9") (class "Default")
      (node (ref "R33") (pin "1") (pinfunction "1_1") (pintype "passive"))
      (node (ref "U9") (pin "P$4") (pinfunction "PA1_P$4") (pintype "bidirectional"))
    )
    (net (code "21") (name "LED1_10") (class "Default")
      (node (ref "R5") (pin "1") (pinfunction "1_1") (pintype "passive"))
      (node (ref "U2") (pin "P$4") (pinfunction "PA1_P$4") (pintype "bidirectional"))
    )
    (net (code "22") (name "LED2") (class "Default")
      (node (ref "R2") (pin "1") (pinfunction "1_1") (pintype "passive"))
      (node (ref "U1") (pin "P$5") (pinfunction "PA2_P$5") (pintype "bidirectional"))
    )
    (net (code "23") (name "LED2_2") (class "Default")
      (node (ref "R38") (pin "1") (pinfunction "1_1") (pintype "passive"))
      (node (ref "U10") (pin "P$5") (pinfunction "PA2_P$5") (pintype "bidirectional"))
    )
    (net (code "24") (name "LED2_3") (class "Default")
      (node (ref "R10") (pin "1") (pinfunction "1_1") (pintype "passive"))
      (node (ref "U3") (pin "P$5") (pinfunction "PA2_P$5") (pintype "bidirectional"))
    )
    (net (code "25") (name "LED2_4") (class "Default")
      (node (ref "R14") (pin "1") (pinfunction "1_1") (pintype "passive"))
      (node (ref "U4") (pin "P$5") (pinfunction "PA2_P$5") (pintype "bidirectional"))
    )
    (net (code "26") (name "LED2_5") (class "Default")
      (node (ref "R18") (pin "1") (pinfunction "1_1") (pintype "passive"))
      (node (ref "U5") (pin "P$5") (pinfunction "PA2_P$5") (pintype "bidirectional"))
    )
    (net (code "27") (name "LED2_6") (class "Default")
      (node (ref "R22") (pin "1") (pinfunction "1_1") (pintype "passive"))
      (node (ref "U6") (pin "P$5") (pinfunction "PA2_P$5") (pintype "bidirectional"))
    )
    (net (code "28") (name "LED2_7") (class "Default")
      (node (ref "R26") (pin "1") (pinfunction "1_1") (pintype "passive"))
      (node (ref "U7") (pin "P$5") (pinfunction "PA2_P$5") (pintype "bidirectional"))
    )
    (net (code "29") (name "LED2_8") (class "Default")
      (node (ref "R30") (pin "1") (pinfunction "1_1") (pintype "passive"))
      (node (ref "U8") (pin "P$5") (pinfunction "PA2_P$5") (pintype "bidirectional"))
    )
    (net (code "30") (name "LED2_9") (class "Default")
      (node (ref "R34") (pin "1") (pinfunction "1_1") (pintype "passive"))
      (node (ref "U9") (pin "P$5") (pinfunction "PA2_P$5") (pintype "bidirectional"))
    )
    (net (code "31") (name "LED2_10") (class "Default")
      (node (ref "R6") (pin "1") (pinfunction "1_1") (pintype "passive"))
      (node (ref "U2") (pin "P$5") (pinfunction "PA2_P$5") (pintype "bidirectional"))
    )
    (net (code "32") (name "LED3") (class "Default")
      (node (ref "R3") (pin "1") (pinfunction "1_1") (pintype "passive"))
      (node (ref "U1") (pin "P$7") (pinfunction "PA3_P$7") (pintype "bidirectional"))
    )
    (net (code "33") (name "LED3_2") (class "Default")
      (node (ref "R39") (pin "1") (pinfunction "1_1") (pintype "passive"))
      (node (ref "U10") (pin "P$7") (pinfunction "PA3_P$7") (pintype "bidirectional"))
    )
    (net (code "34") (name "LED3_3") (class "Default")
      (node (ref "R11") (pin "1") (pinfunction "1_1") (pintype "passive"))
      (node (ref "U3") (pin "P$7") (pinfunction "PA3_P$7") (pintype "bidirectional"))
    )
    (net (code "35") (name "LED3_4") (class "Default")
      (node (ref "R15") (pin "1") (pinfunction "1_1") (pintype "passive"))
      (node (ref "U4") (pin "P$7") (pinfunction "PA3_P$7") (pintype "bidirectional"))
    )
    (net (code "36") (name "LED3_5") (class "Default")
      (node (ref "R19") (pin "1") (pinfunction "1_1") (pintype "passive"))
      (node (ref "U5") (pin "P$7") (pinfunction "PA3_P$7") (pintype "bidirectional"))
    )
    (net (code "37") (name "LED3_6") (class "Default")
      (node (ref "R23") (pin "1") (pinfunction "1_1") (pintype "passive"))
      (node (ref "U6") (pin "P$7") (pinfunction "PA3_P$7") (pintype "bidirectional"))
    )
    (net (code "38") (name "LED3_7") (class "Default")
      (node (ref "R27") (pin "1") (pinfunction "1_1") (pintype "passive"))
      (node (ref "U7") (pin "P$7") (pinfunction "PA3_P$7") (pintype "bidirectional"))
    )
    (net (code "39") (name "LED3_8") (class "Default")
      (node (ref "R31") (pin "1") (pinfunction "1_1") (pintype "passive"))
      (node (ref "U8") (pin "P$7") (pinfunction "PA3_P$7") (pintype "bidirectional"))
    )
    (net (code "40") (name "LED3_9") (class "Default")
      (node (ref "R35") (pin "1") (pinfunction "1_1") (pintype "passive"))
      (node (ref "U9") (pin "P$7") (pinfunction "PA3_P$7") (pintype "bidirectional"))
    )
    (net (code "41") (name "LED3_10") (class "Default")
      (node (ref "R7") (pin "1") (pinfunction "1_1") (pintype "passive"))
      (node (ref "U2") (pin "P$7") (pinfunction "PA3_P$7") (pintype "bidirectional"))
    )
    (net (code "42") (name "Net-(D1-PadP$2)") (class "Default")
      (node (ref "D1") (pin "P$2") (pinfunction "P$2_P$2") (pintype "bidirectional"))
      (node (ref "D2") (pin "P$2") (pinfunction "P$2_P$2") (pintype "bidirectional"))
      (node (ref "R1") (pin "2") (pinfunction "2_2") (pintype "passive"))
    )
    (net (code "43") (name "Net-(D1-PadP$4)") (class "Default")
      (node (ref "D1") (pin "P$4") (pinfunction "P$4_P$4") (pintype "bidirectional"))
      (node (ref "D2") (pin "P$4") (pinfunction "P$4_P$4") (pintype "bidirectional"))
      (node (ref "R2") (pin "2") (pinfunction "2_2") (pintype "passive"))
    )
    (net (code "44") (name "Net-(D1-PadP$6)") (class "Default")
      (node (ref "D1") (pin "P$6") (pinfunction "P$6_P$6") (pintype "bidirectional"))
      (node (ref "D2") (pin "P$6") (pinfunction "P$6_P$6") (pintype "bidirectional"))
      (node (ref "R3") (pin "2") (pinfunction "2_2") (pintype "passive"))
    )
    (net (code "45") (name "Net-(D3-PadP$2)") (class "Default")
      (node (ref "D3") (pin "P$2") (pinfunction "P$2_P$2") (pintype "bidirectional"))
      (node (ref "D4") (pin "P$2") (pinfunction "P$2_P$2") (pintype "bidirectional"))
      (node (ref "R5") (pin "2") (pinfunction "2_2") (pintype "passive"))
    )
    (net (code "46") (name "Net-(D3-PadP$4)") (class "Default")
      (node (ref "D3") (pin "P$4") (pinfunction "P$4_P$4") (pintype "bidirectional"))
      (node (ref "D4") (pin "P$4") (pinfunction "P$4_P$4") (pintype "bidirectional"))
      (node (ref "R6") (pin "2") (pinfunction "2_2") (pintype "passive"))
    )
    (net (code "47") (name "Net-(D3-PadP$6)") (class "Default")
      (node (ref "D3") (pin "P$6") (pinfunction "P$6_P$6") (pintype "bidirectional"))
      (node (ref "D4") (pin "P$6") (pinfunction "P$6_P$6") (pintype "bidirectional"))
      (node (ref "R7") (pin "2") (pinfunction "2_2") (pintype "passive"))
    )
    (net (code "48") (name "Net-(D5-PadP$2)") (class "Default")
      (node (ref "D5") (pin "P$2") (pinfunction "P$2_P$2") (pintype "bidirectional"))
      (node (ref "D6") (pin "P$2") (pinfunction "P$2_P$2") (pintype "bidirectional"))
      (node (ref "R9") (pin "2") (pinfunction "2_2") (pintype "passive"))
    )
    (net (code "49") (name "Net-(D5-PadP$4)") (class "Default")
      (node (ref "D5") (pin "P$4") (pinfunction "P$4_P$4") (pintype "bidirectional"))
      (node (ref "D6") (pin "P$4") (pinfunction "P$4_P$4") (pintype "bidirectional"))
      (node (ref "R10") (pin "2") (pinfunction "2_2") (pintype "passive"))
    )
    (net (code "50") (name "Net-(D5-PadP$6)") (class "Default")
      (node (ref "D5") (pin "P$6") (pinfunction "P$6_P$6") (pintype "bidirectional"))
      (node (ref "D6") (pin "P$6") (pinfunction "P$6_P$6") (pintype "bidirectional"))
      (node (ref "R11") (pin "2") (pinfunction "2_2") (pintype "passive"))
    )
    (net (code "51") (name "Net-(D7-PadP$2)") (class "Default")
      (node (ref "D7") (pin "P$2") (pinfunction "P$2_P$2") (pintype "bidirectional"))
      (node (ref "D8") (pin "P$2") (pinfunction "P$2_P$2") (pintype "bidirectional"))
      (node (ref "R13") (pin "2") (pinfunction "2_2") (pintype "passive"))
    )
    (net (code "52") (name "Net-(D7-PadP$4)") (class "Default")
      (node (ref "D7") (pin "P$4") (pinfunction "P$4_P$4") (pintype "bidirectional"))
      (node (ref "D8") (pin "P$4") (pinfunction "P$4_P$4") (pintype "bidirectional"))
      (node (ref "R14") (pin "2") (pinfunction "2_2") (pintype "passive"))
    )
    (net (code "53") (name "Net-(D7-PadP$6)") (class "Default")
      (node (ref "D7") (pin "P$6") (pinfunction "P$6_P$6") (pintype "bidirectional"))
      (node (ref "D8") (pin "P$6") (pinfunction "P$6_P$6") (pintype "bidirectional"))
      (node (ref "R15") (pin "2") (pinfunction "2_2") (pintype "passive"))
    )
    (net (code "54") (name "Net-(D10-PadP$2)") (class "Default")
      (node (ref "D10") (pin "P$2") (pinfunction "P$2_P$2") (pintype "bidirectional"))
      (node (ref "D9") (pin "P$2") (pinfunction "P$2_P$2") (pintype "bidirectional"))
      (node (ref "R17") (pin "2") (pinfunction "2_2") (pintype "passive"))
    )
    (net (code "55") (name "Net-(D10-PadP$4)") (class "Default")
      (node (ref "D10") (pin "P$4") (pinfunction "P$4_P$4") (pintype "bidirectional"))
      (node (ref "D9") (pin "P$4") (pinfunction "P$4_P$4") (pintype "bidirectional"))
      (node (ref "R18") (pin "2") (pinfunction "2_2") (pintype "passive"))
    )
    (net (code "56") (name "Net-(D10-PadP$6)") (class "Default")
      (node (ref "D10") (pin "P$6") (pinfunction "P$6_P$6") (pintype "bidirectional"))
      (node (ref "D9") (pin "P$6") (pinfunction "P$6_P$6") (pintype "bidirectional"))
      (node (ref "R19") (pin "2") (pinfunction "2_2") (pintype "passive"))
    )
    (net (code "57") (name "Net-(D11-PadP$2)") (class "Default")
      (node (ref "D11") (pin "P$2") (pinfunction "P$2_P$2") (pintype "bidirectional"))
      (node (ref "D12") (pin "P$2") (pinfunction "P$2_P$2") (pintype "bidirectional"))
      (node (ref "R21") (pin "2") (pinfunction "2_2") (pintype "passive"))
    )
    (net (code "58") (name "Net-(D11-PadP$4)") (class "Default")
      (node (ref "D11") (pin "P$4") (pinfunction "P$4_P$4") (pintype "bidirectional"))
      (node (ref "D12") (pin "P$4") (pinfunction "P$4_P$4") (pintype "bidirectional"))
      (node (ref "R22") (pin "2") (pinfunction "2_2") (pintype "passive"))
    )
    (net (code "59") (name "Net-(D11-PadP$6)") (class "Default")
      (node (ref "D11") (pin "P$6") (pinfunction "P$6_P$6") (pintype "bidirectional"))
      (node (ref "D12") (pin "P$6") (pinfunction "P$6_P$6") (pintype "bidirectional"))
      (node (ref "R23") (pin "2") (pinfunction "2_2") (pintype "passive"))
    )
    (net (code "60") (name "Net-(D13-PadP$2)") (class "Default")
      (node (ref "D13") (pin "P$2") (pinfunction "P$2_P$2") (pintype "bidirectional"))
      (node (ref "D14") (pin "P$2") (pinfunction "P$2_P$2") (pintype "bidirectional"))
      (node (ref "R25") (pin "2") (pinfunction "2_2") (pintype "passive"))
    )
    (net (code "61") (name "Net-(D13-PadP$4)") (class "Default")
      (node (ref "D13") (pin "P$4") (pinfunction "P$4_P$4") (pintype "bidirectional"))
      (node (ref "D14") (pin "P$4") (pinfunction "P$4_P$4") (pintype "bidirectional"))
      (node (ref "R26") (pin "2") (pinfunction "2_2") (pintype "passive"))
    )
    (net (code "62") (name "Net-(D13-PadP$6)") (class "Default")
      (node (ref "D13") (pin "P$6") (pinfunction "P$6_P$6") (pintype "bidirectional"))
      (node (ref "D14") (pin "P$6") (pinfunction "P$6_P$6") (pintype "bidirectional"))
      (node (ref "R27") (pin "2") (pinfunction "2_2") (pintype "passive"))
    )
    (net (code "63") (name "Net-(D15-PadP$2)") (class "Default")
      (node (ref "D15") (pin "P$2") (pinfunction "P$2_P$2") (pintype "bidirectional"))
      (node (ref "D16") (pin "P$2") (pinfunction "P$2_P$2") (pintype "bidirectional"))
      (node (ref "R29") (pin "2") (pinfunction "2_2") (pintype "passive"))
    )
    (net (code "64") (name "Net-(D15-PadP$4)") (class "Default")
      (node (ref "D15") (pin "P$4") (pinfunction "P$4_P$4") (pintype "bidirectional"))
      (node (ref "D16") (pin "P$4") (pinfunction "P$4_P$4") (pintype "bidirectional"))
      (node (ref "R30") (pin "2") (pinfunction "2_2") (pintype "passive"))
    )
    (net (code "65") (name "Net-(D15-PadP$6)") (class "Default")
      (node (ref "D15") (pin "P$6") (pinfunction "P$6_P$6") (pintype "bidirectional"))
      (node (ref "D16") (pin "P$6") (pinfunction "P$6_P$6") (pintype "bidirectional"))
      (node (ref "R31") (pin "2") (pinfunction "2_2") (pintype "passive"))
    )
    (net (code "66") (name "Net-(D17-PadP$2)") (class "Default")
      (node (ref "D17") (pin "P$2") (pinfunction "P$2_P$2") (pintype "bidirectional"))
      (node (ref "D18") (pin "P$2") (pinfunction "P$2_P$2") (pintype "bidirectional"))
      (node (ref "R33") (pin "2") (pinfunction "2_2") (pintype "passive"))
    )
    (net (code "67") (name "Net-(D17-PadP$4)") (class "Default")
      (node (ref "D17") (pin "P$4") (pinfunction "P$4_P$4") (pintype "bidirectional"))
      (node (ref "D18") (pin "P$4") (pinfunction "P$4_P$4") (pintype "bidirectional"))
      (node (ref "R34") (pin "2") (pinfunction "2_2") (pintype "passive"))
    )
    (net (code "68") (name "Net-(D17-PadP$6)") (class "Default")
      (node (ref "D17") (pin "P$6") (pinfunction "P$6_P$6") (pintype "bidirectional"))
      (node (ref "D18") (pin "P$6") (pinfunction "P$6_P$6") (pintype "bidirectional"))
      (node (ref "R35") (pin "2") (pinfunction "2_2") (pintype "passive"))
    )
    (net (code "69") (name "Net-(D19-PadP$2)") (class "Default")
      (node (ref "D19") (pin "P$2") (pinfunction "P$2_P$2") (pintype "bidirectional"))
      (node (ref "D20") (pin "P$2") (pinfunction "P$2_P$2") (pintype "bidirectional"))
      (node (ref "R37") (pin "2") (pinfunction "2_2") (pintype "passive"))
    )
    (net (code "70") (name "Net-(D19-PadP$4)") (class "Default")
      (node (ref "D19") (pin "P$4") (pinfunction "P$4_P$4") (pintype "bidirectional"))
      (node (ref "D20") (pin "P$4") (pinfunction "P$4_P$4") (pintype "bidirectional"))
      (node (ref "R38") (pin "2") (pinfunction "2_2") (pintype "passive"))
    )
    (net (code "71") (name "Net-(D19-PadP$6)") (class "Default")
      (node (ref "D19") (pin "P$6") (pinfunction "P$6_P$6") (pintype "bidirectional"))
      (node (ref "D20") (pin "P$6") (pinfunction "P$6_P$6") (pintype "bidirectional"))
      (node (ref "R39") (pin "2") (pinfunction "2_2") (pintype "passive"))
    )
    (net (code "72") (name "RX") (class "Default")
      (node (ref "U1") (pin "P$3") (pinfunction "PA7_P$3") (pintype "bidirectional"))
    )
    (net (code "73") (name "UPDI1") (class "Default")
      (node (ref "J1") (pin "1") (pinfunction "1_1") (pintype "passive"))
      (node (ref "R4") (pin "2") (pinfunction "2_2") (pintype "passive"))
      (node (ref "S1") (pin "2") (pinfunction "1_2") (pintype "passive"))
      (node (ref "S1") (pin "3") (pinfunction "1_3") (pintype "passive"))
      (node (ref "TP25") (pin "P$1") (pinfunction "1_P$1") (pintype "bidirectional"))
      (node (ref "U1") (pin "P$6") (pinfunction "PA0_P$6") (pintype "bidirectional"))
    )
    (net (code "74") (name "UPDI_2") (class "Default")
      (node (ref "J10") (pin "1") (pinfunction "1_1") (pintype "passive"))
      (node (ref "R40") (pin "2") (pinfunction "2_2") (pintype "passive"))
      (node (ref "S10") (pin "2") (pinfunction "1_2") (pintype "passive"))
      (node (ref "S10") (pin "3") (pinfunction "1_3") (pintype "passive"))
      (node (ref "TP22") (pin "P$1") (pinfunction "1_P$1") (pintype "bidirectional"))
      (node (ref "U10") (pin "P$6") (pinfunction "PA0_P$6") (pintype "bidirectional"))
    )
    (net (code "75") (name "UPDI_3") (class "Default")
      (node (ref "J3") (pin "1") (pinfunction "1_1") (pintype "passive"))
      (node (ref "R12") (pin "2") (pinfunction "2_2") (pintype "passive"))
      (node (ref "S3") (pin "2") (pinfunction "1_2") (pintype "passive"))
      (node (ref "S3") (pin "3") (pinfunction "1_3") (pintype "passive"))
      (node (ref "TP19") (pin "P$1") (pinfunction "1_P$1") (pintype "bidirectional"))
      (node (ref "U3") (pin "P$6") (pinfunction "PA0_P$6") (pintype "bidirectional"))
    )
    (net (code "76") (name "UPDI_4") (class "Default")
      (node (ref "J4") (pin "1") (pinfunction "1_1") (pintype "passive"))
      (node (ref "R16") (pin "2") (pinfunction "2_2") (pintype "passive"))
      (node (ref "S4") (pin "2") (pinfunction "1_2") (pintype "passive"))
      (node (ref "S4") (pin "3") (pinfunction "1_3") (pintype "passive"))
      (node (ref "TP16") (pin "P$1") (pinfunction "1_P$1") (pintype "bidirectional"))
      (node (ref "U4") (pin "P$6") (pinfunction "PA0_P$6") (pintype "bidirectional"))
    )
    (net (code "77") (name "UPDI_5") (class "Default")
      (node (ref "J5") (pin "1") (pinfunction "1_1") (pintype "passive"))
      (node (ref "R20") (pin "2") (pinfunction "2_2") (pintype "passive"))
      (node (ref "S5") (pin "2") (pinfunction "1_2") (pintype "passive"))
      (node (ref "S5") (pin "3") (pinfunction "1_3") (pintype "passive"))
      (node (ref "TP13") (pin "P$1") (pinfunction "1_P$1") (pintype "bidirectional"))
      (node (ref "U5") (pin "P$6") (pinfunction "PA0_P$6") (pintype "bidirectional"))
    )
    (net (code "78") (name "UPDI_6") (class "Default")
      (node (ref "J6") (pin "1") (pinfunction "1_1") (pintype "passive"))
      (node (ref "R24") (pin "2") (pinfunction "2_2") (pintype "passive"))
      (node (ref "S6") (pin "2") (pinfunction "1_2") (pintype "passive"))
      (node (ref "S6") (pin "3") (pinfunction "1_3") (pintype "passive"))
      (node (ref "TP10") (pin "P$1") (pinfunction "1_P$1") (pintype "bidirectional"))
      (node (ref "U6") (pin "P$6") (pinfunction "PA0_P$6") (pintype "bidirectional"))
    )
    (net (code "79") (name "UPDI_7") (class "Default")
      (node (ref "J7") (pin "1") (pinfunction "1_1") (pintype "passive"))
      (node (ref "R28") (pin "2") (pinfunction "2_2") (pintype "passive"))
      (node (ref "S7") (pin "2") (pinfunction "1_2") (pintype "passive"))
      (node (ref "S7") (pin "3") (pinfunction "1_3") (pintype "passive"))
      (node (ref "TP7") (pin "P$1") (pinfunction "1_P$1") (pintype "bidirectional"))
      (node (ref "U7") (pin "P$6") (pinfunction "PA0_P$6") (pintype "bidirectional"))
    )
    (net (code "80") (name "UPDI_8") (class "Default")
      (node (ref "J8") (pin "1") (pinfunction "1_1") (pintype "passive"))
      (node (ref "R32") (pin "2") (pinfunction "2_2") (pintype "passive"))
      (node (ref "S8") (pin "2") (pinfunction "1_2") (pintype "passive"))
      (node (ref "S8") (pin "3") (pinfunction "1_3") (pintype "passive"))
      (node (ref "TP4") (pin "P$1") (pinfunction "1_P$1") (pintype "bidirectional"))
      (node (ref "U8") (pin "P$6") (pinfunction "PA0_P$6") (pintype "bidirectional"))
    )
    (net (code "81") (name "UPDI_9") (class "Default")
      (node (ref "J9") (pin "1") (pinfunction "1_1") (pintype "passive"))
      (node (ref "R36") (pin "2") (pinfunction "2_2") (pintype "passive"))
      (node (ref "S9") (pin "2") (pinfunction "1_2") (pintype "passive"))
      (node (ref "S9") (pin "3") (pinfunction "1_3") (pintype "passive"))
      (node (ref "TP28") (pin "P$1") (pinfunction "1_P$1") (pintype "bidirectional"))
      (node (ref "U9") (pin "P$6") (pinfunction "PA0_P$6") (pintype "bidirectional"))
    )
    (net (code "82") (name "UPDI_10") (class "Default")
      (node (ref "J2") (pin "1") (pinfunction "1_1") (pintype "passive"))
      (node (ref "R8") (pin "2") (pinfunction "2_2") (pintype "passive"))
      (node (ref "S2") (pin "2") (pinfunction "1_2") (pintype "passive"))
      (node (ref "S2") (pin "3") (pinfunction "1_3") (pintype "passive"))
      (node (ref "TP1") (pin "P$1") (pinfunction "1_P$1") (pintype "bidirectional"))
      (node (ref "U2") (pin "P$6") (pinfunction "PA0_P$6") (pintype "bidirectional"))
    )
    (net (code "83") (name "VCC") (class "Default")
      (node (ref "C1") (pin "1") (pinfunction "1_1") (pintype "passive"))
      (node (ref "C10") (pin "1") (pinfunction "1_1") (pintype "passive"))
      (node (ref "C2") (pin "1") (pinfunction "1_1") (pintype "passive"))
      (node (ref "C3") (pin "1") (pinfunction "1_1") (pintype "passive"))
      (node (ref "C4") (pin "1") (pinfunction "1_1") (pintype "passive"))
      (node (ref "C5") (pin "1") (pinfunction "1_1") (pintype "passive"))
      (node (ref "C6") (pin "1") (pinfunction "1_1") (pintype "passive"))
      (node (ref "C7") (pin "1") (pinfunction "1_1") (pintype "passive"))
      (node (ref "C8") (pin "1") (pinfunction "1_1") (pintype "passive"))
      (node (ref "C9") (pin "1") (pinfunction "1_1") (pintype "passive"))
      (node (ref "J1") (pin "2") (pinfunction "2_2") (pintype "passive"))
      (node (ref "J10") (pin "2") (pinfunction "2_2") (pintype "passive"))
      (node (ref "J2") (pin "2") (pinfunction "2_2") (pintype "passive"))
      (node (ref "J3") (pin "2") (pinfunction "2_2") (pintype "passive"))
      (node (ref "J4") (pin "2") (pinfunction "2_2") (pintype "passive"))
      (node (ref "J5") (pin "2") (pinfunction "2_2") (pintype "passive"))
      (node (ref "J6") (pin "2") (pinfunction "2_2") (pintype "passive"))
      (node (ref "J7") (pin "2") (pinfunction "2_2") (pintype "passive"))
      (node (ref "J8") (pin "2") (pinfunction "2_2") (pintype "passive"))
      (node (ref "J9") (pin "2") (pinfunction "2_2") (pintype "passive"))
      (node (ref "S1") (pin "1") (pinfunction "2_1") (pintype "passive"))
      (node (ref "S1") (pin "4") (pinfunction "2_4") (pintype "passive"))
      (node (ref "S10") (pin "1") (pinfunction "2_1") (pintype "passive"))
      (node (ref "S10") (pin "4") (pinfunction "2_4") (pintype "passive"))
      (node (ref "S2") (pin "1") (pinfunction "2_1") (pintype "passive"))
      (node (ref "S2") (pin "4") (pinfunction "2_4") (pintype "passive"))
      (node (ref "S3") (pin "1") (pinfunction "2_1") (pintype "passive"))
      (node (ref "S3") (pin "4") (pinfunction "2_4") (pintype "passive"))
      (node (ref "S4") (pin "1") (pinfunction "2_1") (pintype "passive"))
      (node (ref "S4") (pin "4") (pinfunction "2_4") (pintype "passive"))
      (node (ref "S5") (pin "1") (pinfunction "2_1") (pintype "passive"))
      (node (ref "S5") (pin "4") (pinfunction "2_4") (pintype "passive"))
      (node (ref "S6") (pin "1") (pinfunction "2_1") (pintype "passive"))
      (node (ref "S6") (pin "4") (pinfunction "2_4") (pintype "passive"))
      (node (ref "S7") (pin "1") (pinfunction "2_1") (pintype "passive"))
      (node (ref "S7") (pin "4") (pinfunction "2_4") (pintype "passive"))
      (node (ref "S8") (pin "1") (pinfunction "2_1") (pintype "passive"))
      (node (ref "S8") (pin "4") (pinfunction "2_4") (pintype "passive"))
      (node (ref "S9") (pin "1") (pinfunction "2_1") (pintype "passive"))
      (node (ref "S9") (pin "4") (pinfunction "2_4") (pintype "passive"))
      (node (ref "TP11") (pin "P$1") (pinfunction "1_P$1") (pintype "bidirectional"))
      (node (ref "TP14") (pin "P$1") (pinfunction "1_P$1") (pintype "bidirectional"))
      (node (ref "TP17") (pin "P$1") (pinfunction "1_P$1") (pintype "bidirectional"))
      (node (ref "TP2") (pin "P$1") (pinfunction "1_P$1") (pintype "bidirectional"))
      (node (ref "TP20") (pin "P$1") (pinfunction "1_P$1") (pintype "bidirectional"))
      (node (ref "TP23") (pin "P$1") (pinfunction "1_P$1") (pintype "bidirectional"))
      (node (ref "TP26") (pin "P$1") (pinfunction "1_P$1") (pintype "bidirectional"))
      (node (ref "TP29") (pin "P$1") (pinfunction "1_P$1") (pintype "bidirectional"))
      (node (ref "TP5") (pin "P$1") (pinfunction "1_P$1") (pintype "bidirectional"))
      (node (ref "TP8") (pin "P$1") (pinfunction "1_P$1") (pintype "bidirectional"))
      (node (ref "U1") (pin "P$1") (pinfunction "VDD_P$1") (pintype "bidirectional"))
      (node (ref "U10") (pin "P$1") (pinfunction "VDD_P$1") (pintype "bidirectional"))
      (node (ref "U2") (pin "P$1") (pinfunction "VDD_P$1") (pintype "bidirectional"))
      (node (ref "U3") (pin "P$1") (pinfunction "VDD_P$1") (pintype "bidirectional"))
      (node (ref "U4") (pin "P$1") (pinfunction "VDD_P$1") (pintype "bidirectional"))
      (node (ref "U5") (pin "P$1") (pinfunction "VDD_P$1") (pintype "bidirectional"))
      (node (ref "U6") (pin "P$1") (pinfunction "VDD_P$1") (pintype "bidirectional"))
      (node (ref "U7") (pin "P$1") (pinfunction "VDD_P$1") (pintype "bidirectional"))
      (node (ref "U8") (pin "P$1") (pinfunction "VDD_P$1") (pintype "bidirectional"))
      (node (ref "U9") (pin "P$1") (pinfunction "VDD_P$1") (pintype "bidirectional"))
    )
  )
)
